# CHIP_dispv3_0.net
KiCad netlist of a schematic drawn in EAGLE
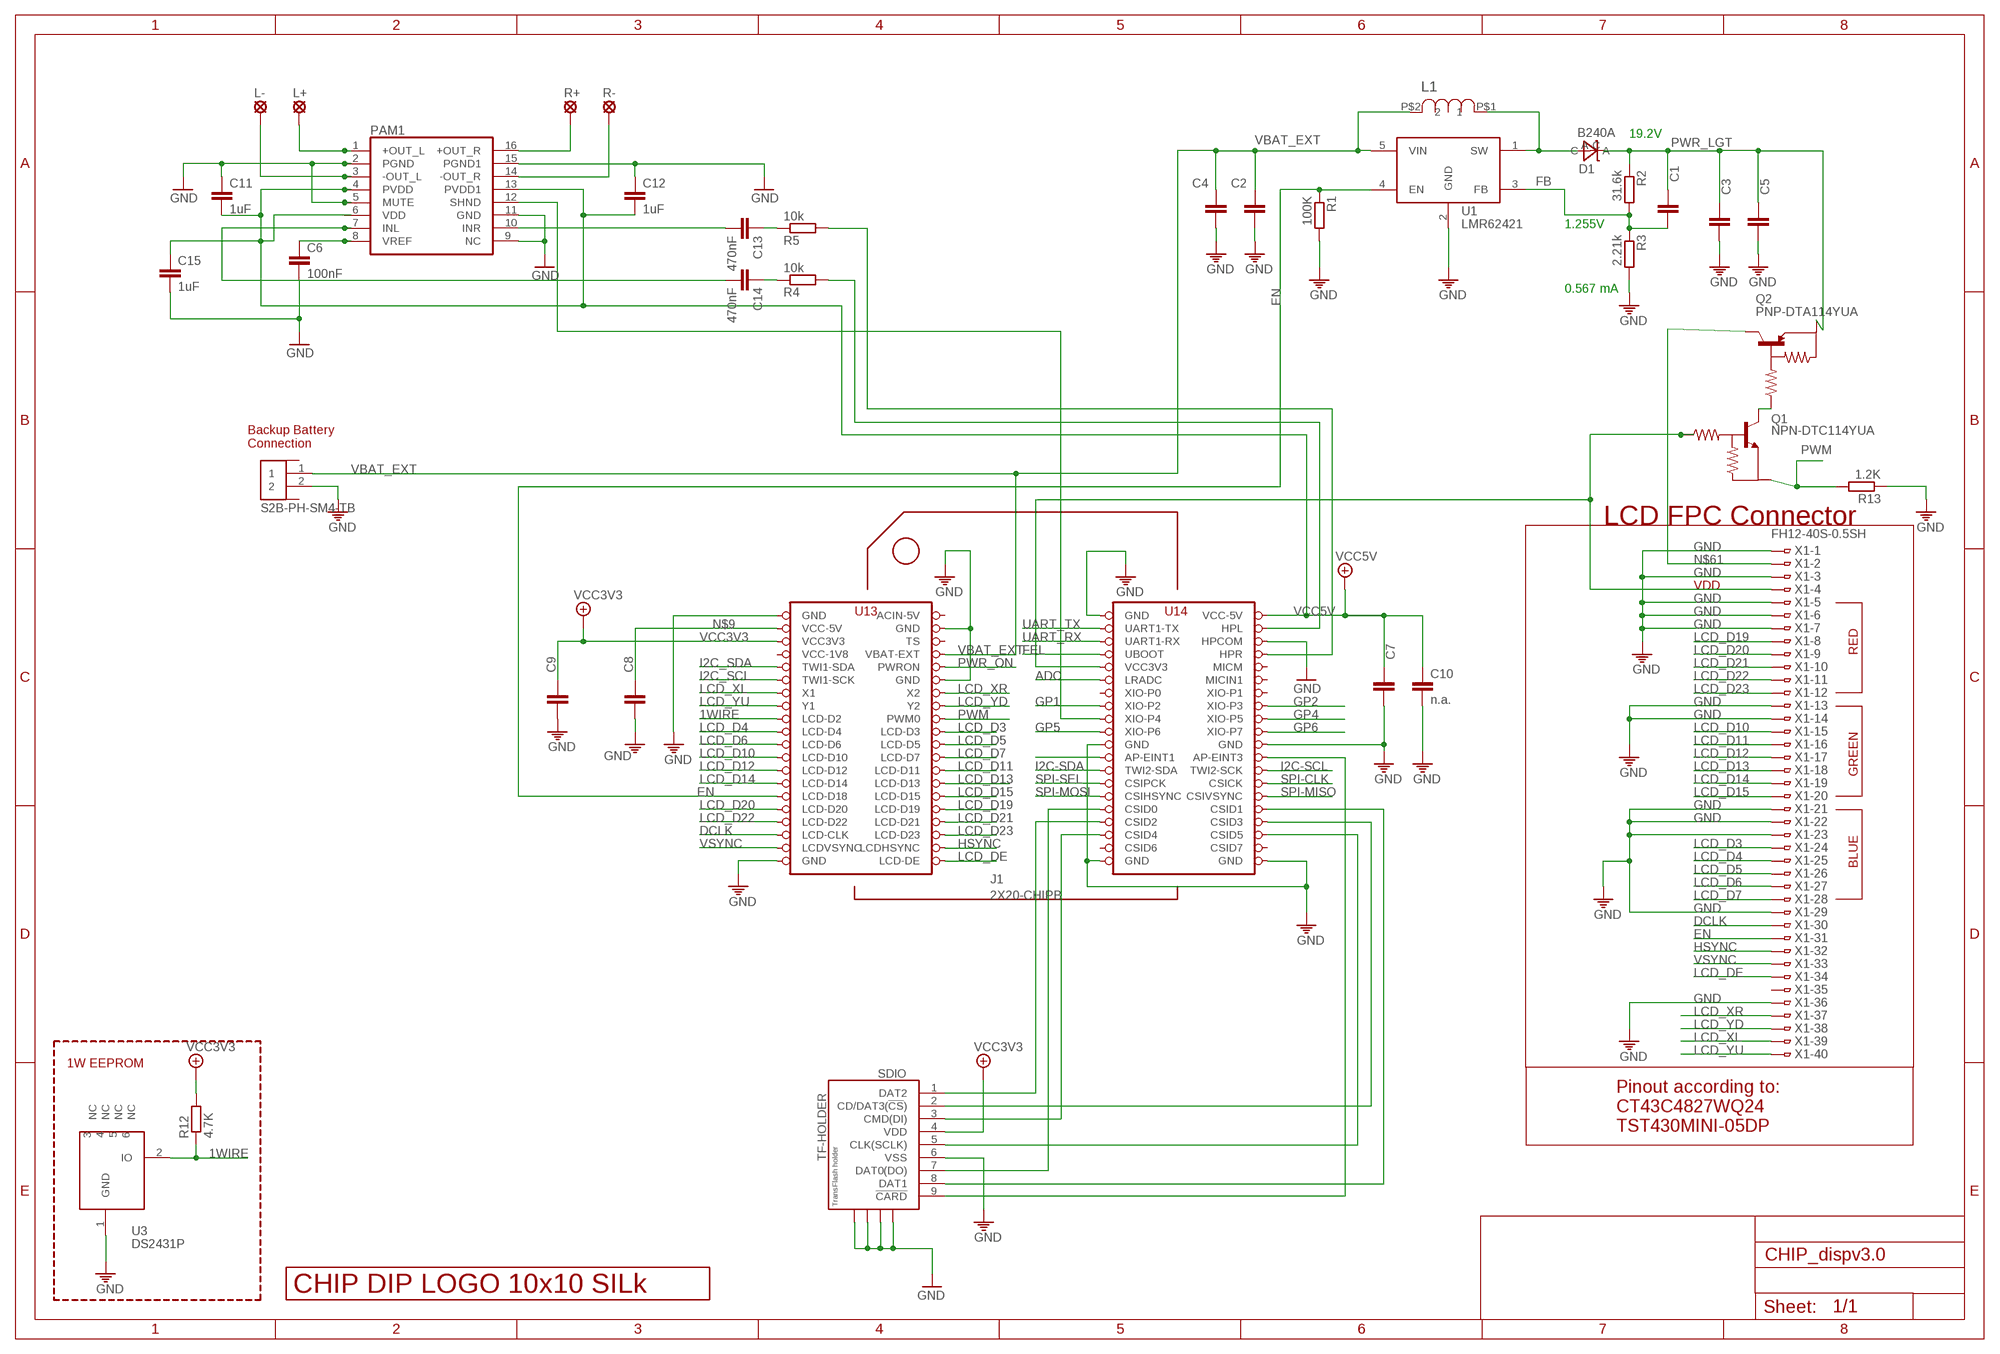
[diagram p0: schematic, sheet 1]

(export (version "E")
  (design (tool "Eeschema 10.0.6"))
  (components
    (comp (ref "C1")
      (value "220pF")
      (footprint "eagle-import:C0805")
      (libsource (lib "eagle-import") (part "C-EUC0805"))
    )
    (comp (ref "C2")
      (value "100nF")
      (footprint "eagle-import:C0805")
      (libsource (lib "eagle-import") (part "C-EUC0805"))
    )
    (comp (ref "C3")
      (value "100nF")
      (footprint "eagle-import:C0805")
      (libsource (lib "eagle-import") (part "C-EUC0805"))
    )
    (comp (ref "C4")
      (value "22uF")
      (footprint "eagle-import:C0805")
      (libsource (lib "eagle-import") (part "C-EUC0805"))
    )
    (comp (ref "C5")
      (value "22uF")
      (footprint "eagle-import:C0805")
      (libsource (lib "eagle-import") (part "C-EUC0805"))
    )
    (comp (ref "C6")
      (value "100nF")
      (footprint "eagle-import:C0805")
      (libsource (lib "eagle-import") (part "C-EUC0805"))
    )
    (comp (ref "C7")
      (value "n.a.")
      (footprint "eagle-import:C0805")
      (libsource (lib "eagle-import") (part "C-EUC0805"))
    )
    (comp (ref "C8")
      (value "100nF")
      (footprint "eagle-import:C0805")
      (libsource (lib "eagle-import") (part "C-EUC0805"))
    )
    (comp (ref "C9")
      (value "100nF")
      (footprint "eagle-import:C0805")
      (libsource (lib "eagle-import") (part "C-EUC0805"))
    )
    (comp (ref "C10")
      (value "n.a.")
      (footprint "eagle-import:C0805")
      (libsource (lib "eagle-import") (part "C-EUC0805"))
    )
    (comp (ref "C11")
      (value "1uF")
      (footprint "eagle-import:C0805")
      (libsource (lib "eagle-import") (part "C-EUC0805"))
    )
    (comp (ref "C12")
      (value "1uF")
      (footprint "eagle-import:C0805")
      (libsource (lib "eagle-import") (part "C-EUC0805"))
    )
    (comp (ref "C13")
      (value "470nF")
      (footprint "eagle-import:C0805")
      (libsource (lib "eagle-import") (part "C-EUC0805"))
    )
    (comp (ref "C14")
      (value "470nF")
      (footprint "eagle-import:C0805")
      (libsource (lib "eagle-import") (part "C-EUC0805"))
    )
    (comp (ref "C15")
      (value "1uF")
      (footprint "eagle-import:C0805")
      (libsource (lib "eagle-import") (part "C-EUC0805"))
    )
    (comp (ref "D1")
      (value "B240A")
      (footprint "eagle-import:DO-214AC")
      (fields (field (name "MFG") "DIGIKEY") (field (name "VENDOR_PART_NUMBER") "B240A-13-F"))
      (libsource (lib "eagle-import") (part "DIODE_SCHTKY_B240"))
    )
    (comp (ref "J1")
      (value "2X20-CHIPB")
      (footprint "eagle-import:2X20CHIP_SM")
      (libsource (lib "eagle-import") (part "2X20-CHIPB"))
    )
    (comp (ref "J3")
      (value "S2B-PH-SM4-TB")
      (footprint "eagle-import:S2B-PH-SM4-TB")
      (fields (field (name "MFG") "DIGIKEY") (field (name "VENDOR_PART_NUMBER") "S2B-PH-SM4-TB(LF)(SN)"))
      (libsource (lib "eagle-import") (part "S2B-PH-SM4-TB"))
    )
    (comp (ref "L+")
      (value "SE11")
      (footprint "eagle-import:SE11")
      (libsource (lib "eagle-import") (part "SE11"))
    )
    (comp (ref "L-")
      (value "SE11")
      (footprint "eagle-import:SE11")
      (libsource (lib "eagle-import") (part "SE11"))
    )
    (comp (ref "L1")
      (value "SRN6045-100M")
      (footprint "eagle-import:SRN6045")
      (fields (field (name "MFG") "DIGIKEY"))
      (libsource (lib "eagle-import") (part "SRN6045-100M"))
    )
    (comp (ref "PAM1")
      (value "PAM8403")
      (footprint "eagle-import:SOP-16")
      (libsource (lib "eagle-import") (part "PAM8403"))
    )
    (comp (ref "Q1")
      (value "NPN-DTC114YUA")
      (footprint "eagle-import:SOT323")
      (libsource (lib "eagle-import") (part "NPN-DTC114YUA"))
    )
    (comp (ref "Q2")
      (value "PNP-DTA114YUA")
      (footprint "eagle-import:SOT323")
      (libsource (lib "eagle-import") (part "PNP-DTA114YUA"))
    )
    (comp (ref "R+")
      (value "SE11")
      (footprint "eagle-import:SE11")
      (libsource (lib "eagle-import") (part "SE11"))
    )
    (comp (ref "R-")
      (value "SE11")
      (footprint "eagle-import:SE11")
      (libsource (lib "eagle-import") (part "SE11"))
    )
    (comp (ref "R1")
      (value "100K")
      (footprint "eagle-import:M0805")
      (libsource (lib "eagle-import") (part "R-EU_M0805"))
    )
    (comp (ref "R2")
      (value "31.6k")
      (footprint "eagle-import:M0805")
      (libsource (lib "eagle-import") (part "R-EU_M0805"))
    )
    (comp (ref "R3")
      (value "2.21k")
      (footprint "eagle-import:M0805")
      (libsource (lib "eagle-import") (part "R-EU_M0805"))
    )
    (comp (ref "R4")
      (value "10k")
      (footprint "eagle-import:R0805")
      (libsource (lib "eagle-import") (part "R-EU_R0805"))
    )
    (comp (ref "R5")
      (value "10k")
      (footprint "eagle-import:R0805")
      (libsource (lib "eagle-import") (part "R-EU_R0805"))
    )
    (comp (ref "R12")
      (value "4.7K")
      (footprint "eagle-import:M0805")
      (libsource (lib "eagle-import") (part "R-EU_M0805"))
    )
    (comp (ref "R13")
      (value "1.2K")
      (footprint "eagle-import:M0805")
      (libsource (lib "eagle-import") (part "R-EU_M0805"))
    )
    (comp (ref "SDIO")
      (value "TF-HOLDER")
      (footprint "eagle-import:TF-PULL")
      (libsource (lib "eagle-import") (part "TF-HOLDER"))
    )
    (comp (ref "U$2")
      (value "LOGO_10X10_SILK")
      (footprint "eagle-import:LOGO2_10X10_SILK")
      (libsource (lib "eagle-import") (part "LOGO_10X10_SILK"))
    )
    (comp (ref "U1")
      (value "LMR62421")
      (footprint "eagle-import:SOT23-5")
      (fields (field (name "MFG") "DIGIKEY") (field (name "VENDOR_PART_NUMBER") "LMR62421XMFE/NOPB"))
      (libsource (lib "eagle-import") (part "LMR62421"))
    )
    (comp (ref "U3")
      (value "DS2431P")
      (footprint "eagle-import:TSOC6")
      (fields (field (name "MFG") "DIGIKEY") (field (name "VENDOR_PART_NUMBER") "DS2431P+T&R"))
      (libsource (lib "eagle-import") (part "DS2431P"))
    )
    (comp (ref "X1")
      (value "FH12-40S-0.5SH")
      (footprint "eagle-import:FH12-40S-0.5SH")
      (fields (field (name "MFG") "DIGIKEY") (field (name "VENDOR_PART_NUMBER") "FH12-40S-0.5SH(55)"))
      (libsource (lib "eagle-import") (part "FH12-40S-0.5SH"))
    )
  )
  (nets
    (net (code "1") (name "/1WIRE") (class "Default")
      (node (ref "J1") (pin "LCD-D2") (pinfunction "LCD-D2_LCD-D2") (pintype "passive"))
      (node (ref "R12") (pin "1") (pinfunction "1_1") (pintype "passive"))
      (node (ref "U3") (pin "2") (pinfunction "IO_2") (pintype "bidirectional"))
    )
    (net (code "2") (name "/ADC") (class "Default")
      (node (ref "J1") (pin "LRADC") (pinfunction "LRADC_LRADC") (pintype "passive"))
    )
    (net (code "3") (name "/DCLK") (class "Default")
      (node (ref "J1") (pin "LCD-CLK") (pinfunction "LCD-CLK_LCD-CLK") (pintype "passive"))
      (node (ref "X1") (pin "30") (pinfunction "1_30") (pintype "passive"))
    )
    (net (code "4") (name "/EN") (class "Default")
      (node (ref "J1") (pin "LCD-D18") (pinfunction "LCD-D18_LCD-D18") (pintype "passive"))
      (node (ref "R1") (pin "1") (pinfunction "1_1") (pintype "passive"))
      (node (ref "U1") (pin "4") (pinfunction "EN_4") (pintype "bidirectional"))
      (node (ref "X1") (pin "31") (pinfunction "1_31") (pintype "passive"))
    )
    (net (code "5") (name "/FB") (class "Default")
      (node (ref "C1") (pin "2") (pinfunction "2_2") (pintype "passive"))
      (node (ref "R2") (pin "2") (pinfunction "2_2") (pintype "passive"))
      (node (ref "R3") (pin "1") (pinfunction "1_1") (pintype "passive"))
      (node (ref "U1") (pin "3") (pinfunction "FB_3") (pintype "bidirectional"))
    )
    (net (code "6") (name "/FEL") (class "Default")
      (node (ref "J1") (pin "FEL") (pinfunction "UBOOT_FEL") (pintype "passive"))
    )
    (net (code "7") (name "/GP1") (class "Default")
      (node (ref "J1") (pin "XIO-P2") (pinfunction "XIO-P2_XIO-P2") (pintype "passive"))
    )
    (net (code "8") (name "/GP2") (class "Default")
      (node (ref "J1") (pin "XIO-P3") (pinfunction "XIO-P3_XIO-P3") (pintype "passive"))
    )
    (net (code "9") (name "/GP4") (class "Default")
      (node (ref "J1") (pin "XIO-P5") (pinfunction "XIO-P5_XIO-P5") (pintype "passive"))
    )
    (net (code "10") (name "/GP5") (class "Default")
      (node (ref "J1") (pin "XIO-P6") (pinfunction "XIO-P6_XIO-P6") (pintype "passive"))
    )
    (net (code "11") (name "/GP6") (class "Default")
      (node (ref "J1") (pin "XIO-P7") (pinfunction "XIO-P7_XIO-P7") (pintype "passive"))
    )
    (net (code "12") (name "/HSYNC") (class "Default")
      (node (ref "J1") (pin "LCD-HSYNC") (pinfunction "LCDHSYNC_LCD-HSYNC") (pintype "passive"))
      (node (ref "X1") (pin "32") (pinfunction "1_32") (pintype "passive"))
    )
    (net (code "13") (name "/I2C-SCL") (class "Default")
      (node (ref "J1") (pin "TWI2-SCK") (pinfunction "TWI2-SCK_TWI2-SCK") (pintype "passive"))
    )
    (net (code "14") (name "/I2C-SDA") (class "Default")
      (node (ref "J1") (pin "TWI2-SDA") (pinfunction "TWI2-SDA_TWI2-SDA") (pintype "passive"))
    )
    (net (code "15") (name "/I2C_SCL") (class "Default")
      (node (ref "J1") (pin "TWI1-SCK") (pinfunction "TWI1-SCK_TWI1-SCK") (pintype "passive"))
    )
    (net (code "16") (name "/I2C_SDA") (class "Default")
      (node (ref "J1") (pin "TWI1-SDA") (pinfunction "TWI1-SDA_TWI1-SDA") (pintype "passive"))
    )
    (net (code "17") (name "/LCD_D3") (class "Default")
      (node (ref "J1") (pin "LCD-D3") (pinfunction "LCD-D3_LCD-D3") (pintype "passive"))
      (node (ref "X1") (pin "24") (pinfunction "1_24") (pintype "passive"))
    )
    (net (code "18") (name "/LCD_D4") (class "Default")
      (node (ref "J1") (pin "LCD-D4") (pinfunction "LCD-D4_LCD-D4") (pintype "passive"))
      (node (ref "X1") (pin "25") (pinfunction "1_25") (pintype "passive"))
    )
    (net (code "19") (name "/LCD_D5") (class "Default")
      (node (ref "J1") (pin "LCD-D5") (pinfunction "LCD-D5_LCD-D5") (pintype "passive"))
      (node (ref "X1") (pin "26") (pinfunction "1_26") (pintype "passive"))
    )
    (net (code "20") (name "/LCD_D6") (class "Default")
      (node (ref "J1") (pin "LCD-D6") (pinfunction "LCD-D6_LCD-D6") (pintype "passive"))
      (node (ref "X1") (pin "27") (pinfunction "1_27") (pintype "passive"))
    )
    (net (code "21") (name "/LCD_D7") (class "Default")
      (node (ref "J1") (pin "LCD-D7") (pinfunction "LCD-D7_LCD-D7") (pintype "passive"))
      (node (ref "X1") (pin "28") (pinfunction "1_28") (pintype "passive"))
    )
    (net (code "22") (name "/LCD_D10") (class "Default")
      (node (ref "J1") (pin "LCD-D10") (pinfunction "LCD-D10_LCD-D10") (pintype "passive"))
      (node (ref "X1") (pin "15") (pinfunction "1_15") (pintype "passive"))
    )
    (net (code "23") (name "/LCD_D11") (class "Default")
      (node (ref "J1") (pin "LCD-D11") (pinfunction "LCD-D11_LCD-D11") (pintype "passive"))
      (node (ref "X1") (pin "16") (pinfunction "1_16") (pintype "passive"))
    )
    (net (code "24") (name "/LCD_D12") (class "Default")
      (node (ref "J1") (pin "LCD-D12") (pinfunction "LCD-D12_LCD-D12") (pintype "passive"))
      (node (ref "X1") (pin "17") (pinfunction "1_17") (pintype "passive"))
    )
    (net (code "25") (name "/LCD_D13") (class "Default")
      (node (ref "J1") (pin "LCD-D13") (pinfunction "LCD-D13_LCD-D13") (pintype "passive"))
      (node (ref "X1") (pin "18") (pinfunction "1_18") (pintype "passive"))
    )
    (net (code "26") (name "/LCD_D14") (class "Default")
      (node (ref "J1") (pin "LCD-D14") (pinfunction "LCD-D14_LCD-D14") (pintype "passive"))
      (node (ref "X1") (pin "19") (pinfunction "1_19") (pintype "passive"))
    )
    (net (code "27") (name "/LCD_D15") (class "Default")
      (node (ref "J1") (pin "LCD-D15") (pinfunction "LCD-D15_LCD-D15") (pintype "passive"))
      (node (ref "X1") (pin "20") (pinfunction "1_20") (pintype "passive"))
    )
    (net (code "28") (name "/LCD_D19") (class "Default")
      (node (ref "J1") (pin "LCD-D19") (pinfunction "LCD-D19_LCD-D19") (pintype "passive"))
      (node (ref "X1") (pin "8") (pinfunction "1_8") (pintype "passive"))
    )
    (net (code "29") (name "/LCD_D20") (class "Default")
      (node (ref "J1") (pin "LCD-D20") (pinfunction "LCD-D20_LCD-D20") (pintype "passive"))
      (node (ref "X1") (pin "9") (pinfunction "1_9") (pintype "passive"))
    )
    (net (code "30") (name "/LCD_D21") (class "Default")
      (node (ref "J1") (pin "LCD-D21") (pinfunction "LCD-D21_LCD-D21") (pintype "passive"))
      (node (ref "X1") (pin "10") (pinfunction "1_10") (pintype "passive"))
    )
    (net (code "31") (name "/LCD_D22") (class "Default")
      (node (ref "J1") (pin "LCD-D22") (pinfunction "LCD-D22_LCD-D22") (pintype "passive"))
      (node (ref "X1") (pin "11") (pinfunction "1_11") (pintype "passive"))
    )
    (net (code "32") (name "/LCD_D23") (class "Default")
      (node (ref "J1") (pin "LCD-D23") (pinfunction "LCD-D23_LCD-D23") (pintype "passive"))
      (node (ref "X1") (pin "12") (pinfunction "1_12") (pintype "passive"))
    )
    (net (code "33") (name "/LCD_DE") (class "Default")
      (node (ref "J1") (pin "LCD-DE") (pinfunction "LCD-DE_LCD-DE") (pintype "passive"))
      (node (ref "X1") (pin "34") (pinfunction "1_34") (pintype "passive"))
    )
    (net (code "34") (name "/LCD_XL") (class "Default")
      (node (ref "J1") (pin "X1") (pinfunction "X1_X1") (pintype "passive"))
      (node (ref "X1") (pin "39") (pinfunction "1_39") (pintype "passive"))
    )
    (net (code "35") (name "/LCD_XR") (class "Default")
      (node (ref "J1") (pin "X2") (pinfunction "X2_X2") (pintype "passive"))
      (node (ref "X1") (pin "37") (pinfunction "1_37") (pintype "passive"))
    )
    (net (code "36") (name "/LCD_YD") (class "Default")
      (node (ref "J1") (pin "Y2") (pinfunction "Y2_Y2") (pintype "passive"))
      (node (ref "X1") (pin "38") (pinfunction "1_38") (pintype "passive"))
    )
    (net (code "37") (name "/LCD_YU") (class "Default")
      (node (ref "J1") (pin "Y1") (pinfunction "Y1_Y1") (pintype "passive"))
      (node (ref "X1") (pin "40") (pinfunction "1_40") (pintype "passive"))
    )
    (net (code "38") (name "/N$9") (class "Default")
      (node (ref "C8") (pin "1") (pinfunction "1_1") (pintype "passive"))
      (node (ref "J1") (pin "VCC5V@0") (pinfunction "VCC-5V_VCC5V@0") (pintype "power_in"))
    )
    (net (code "39") (name "/N$61") (class "Default")
      (node (ref "Q2") (pin "3") (pinfunction "OUT_3") (pintype "passive"))
      (node (ref "X1") (pin "2") (pinfunction "1_2") (pintype "passive"))
    )
    (net (code "40") (name "/PWM") (class "Default")
      (node (ref "J1") (pin "PWM0") (pinfunction "PWM0_PWM0") (pintype "passive"))
      (node (ref "Q1") (pin "2") (pinfunction "GND_2") (pintype "passive"))
      (node (ref "R13") (pin "2") (pinfunction "2_2") (pintype "passive"))
    )
    (net (code "41") (name "/PWR_LGT") (class "Default")
      (node (ref "C1") (pin "1") (pinfunction "1_1") (pintype "passive"))
      (node (ref "C3") (pin "1") (pinfunction "1_1") (pintype "passive"))
      (node (ref "C5") (pin "1") (pinfunction "1_1") (pintype "passive"))
      (node (ref "D1") (pin "C") (pinfunction "C_C") (pintype "bidirectional"))
      (node (ref "Q2") (pin "2") (pinfunction "GND_2") (pintype "passive"))
      (node (ref "R2") (pin "1") (pinfunction "1_1") (pintype "passive"))
    )
    (net (code "42") (name "/PWR_ON") (class "Default")
      (node (ref "J1") (pin "PWRON") (pinfunction "PWRON_PWRON") (pintype "passive"))
    )
    (net (code "43") (name "/SPI-CLK") (class "Default")
      (node (ref "J1") (pin "CSICK") (pinfunction "CSICK_CSICK") (pintype "passive"))
    )
    (net (code "44") (name "/SPI-MISO") (class "Default")
      (node (ref "J1") (pin "CSIVSYNC") (pinfunction "CSIVSYNC_CSIVSYNC") (pintype "passive"))
    )
    (net (code "45") (name "/SPI-MOSI") (class "Default")
      (node (ref "J1") (pin "CSIHSYNC") (pinfunction "CSIHSYNC_CSIHSYNC") (pintype "passive"))
    )
    (net (code "46") (name "/SPI-SEL") (class "Default")
      (node (ref "J1") (pin "CSIPCK") (pinfunction "CSIPCK_CSIPCK") (pintype "passive"))
    )
    (net (code "47") (name "/UART_RX") (class "Default")
      (node (ref "J1") (pin "UART1-RX") (pinfunction "UART1-RX_UART1-RX") (pintype "passive"))
    )
    (net (code "48") (name "/UART_TX") (class "Default")
      (node (ref "J1") (pin "UART1-TX") (pinfunction "UART1-TX_UART1-TX") (pintype "passive"))
    )
    (net (code "49") (name "/VBAT_EXT") (class "Default")
      (node (ref "C2") (pin "1") (pinfunction "1_1") (pintype "passive"))
      (node (ref "C4") (pin "1") (pinfunction "1_1") (pintype "passive"))
      (node (ref "J1") (pin "BAT") (pinfunction "VBAT-EXT_BAT") (pintype "passive"))
      (node (ref "J3") (pin "1") (pinfunction "1_1") (pintype "bidirectional"))
      (node (ref "L1") (pin "P$2") (pinfunction "2_P$2") (pintype "passive"))
      (node (ref "U1") (pin "5") (pinfunction "VIN_5") (pintype "bidirectional"))
    )
    (net (code "50") (name "/VCC-1V8") (class "Default")
      (node (ref "J1") (pin "VCC1V8") (pinfunction "VCC-1V8_VCC1V8") (pintype "power_in"))
    )
    (net (code "51") (name "/VSYNC") (class "Default")
      (node (ref "J1") (pin "LCD-VSYNC") (pinfunction "LCDVSYNC_LCD-VSYNC") (pintype "passive"))
      (node (ref "X1") (pin "33") (pinfunction "1_33") (pintype "passive"))
    )
    (net (code "52") (name "GND") (class "Default")
      (node (ref "C10") (pin "2") (pinfunction "2_2") (pintype "passive"))
      (node (ref "C11") (pin "1") (pinfunction "1_1") (pintype "passive"))
      (node (ref "C12") (pin "1") (pinfunction "1_1") (pintype "passive"))
      (node (ref "C15") (pin "2") (pinfunction "2_2") (pintype "passive"))
      (node (ref "C2") (pin "2") (pinfunction "2_2") (pintype "passive"))
      (node (ref "C3") (pin "2") (pinfunction "2_2") (pintype "passive"))
      (node (ref "C4") (pin "2") (pinfunction "2_2") (pintype "passive"))
      (node (ref "C5") (pin "2") (pinfunction "2_2") (pintype "passive"))
      (node (ref "C6") (pin "2") (pinfunction "2_2") (pintype "passive"))
      (node (ref "C7") (pin "2") (pinfunction "2_2") (pintype "passive"))
      (node (ref "C8") (pin "2") (pinfunction "2_2") (pintype "passive"))
      (node (ref "C9") (pin "2") (pinfunction "2_2") (pintype "passive"))
      (node (ref "J1") (pin "GND@1") (pinfunction "GND_GND@1") (pintype "power_in"))
      (node (ref "J1") (pin "GND@10") (pinfunction "GND_GND@10") (pintype "power_in"))
      (node (ref "J1") (pin "GND@2") (pinfunction "GND_GND@2") (pintype "power_in"))
      (node (ref "J1") (pin "GND@3") (pinfunction "GND_GND@3") (pintype "power_in"))
      (node (ref "J1") (pin "GND@4") (pinfunction "GND_GND@4") (pintype "power_in"))
      (node (ref "J1") (pin "GND@5") (pinfunction "GND_GND@5") (pintype "power_in"))
      (node (ref "J1") (pin "GND@6") (pinfunction "GND_GND@6") (pintype "power_in"))
      (node (ref "J1") (pin "GND@7") (pinfunction "GND_GND@7") (pintype "power_in"))
      (node (ref "J1") (pin "GND@8") (pinfunction "GND_GND@8") (pintype "power_in"))
      (node (ref "J1") (pin "HPCOM") (pinfunction "HPCOM_HPCOM") (pintype "passive"))
      (node (ref "J3") (pin "2") (pinfunction "2_2") (pintype "bidirectional"))
      (node (ref "PAM1") (pin "11") (pinfunction "GND_11") (pintype "output"))
      (node (ref "PAM1") (pin "15") (pinfunction "PGND1_15") (pintype "output"))
      (node (ref "PAM1") (pin "2") (pinfunction "PGND_2") (pintype "input"))
      (node (ref "PAM1") (pin "5") (pinfunction "MUTE_5") (pintype "input"))
      (node (ref "PAM1") (pin "9") (pinfunction "NC_9") (pintype "output"))
      (node (ref "R1") (pin "2") (pinfunction "2_2") (pintype "passive"))
      (node (ref "R13") (pin "1") (pinfunction "1_1") (pintype "passive"))
      (node (ref "R3") (pin "2") (pinfunction "2_2") (pintype "passive"))
      (node (ref "SDIO") (pin "6") (pinfunction "VSS_6") (pintype "power_in"))
      (node (ref "SDIO") (pin "S1") (pinfunction "S1_S1") (pintype "passive"))
      (node (ref "SDIO") (pin "S2") (pinfunction "S2_S2") (pintype "passive"))
      (node (ref "SDIO") (pin "S3") (pinfunction "S3_S3") (pintype "passive"))
      (node (ref "SDIO") (pin "S4") (pinfunction "S4_S4") (pintype "passive"))
      (node (ref "U1") (pin "2") (pinfunction "GND_2") (pintype "bidirectional"))
      (node (ref "U3") (pin "1") (pinfunction "GND_1") (pintype "bidirectional"))
      (node (ref "X1") (pin "1") (pinfunction "1_1") (pintype "passive"))
      (node (ref "X1") (pin "13") (pinfunction "1_13") (pintype "passive"))
      (node (ref "X1") (pin "14") (pinfunction "1_14") (pintype "passive"))
      (node (ref "X1") (pin "21") (pinfunction "1_21") (pintype "passive"))
      (node (ref "X1") (pin "22") (pinfunction "1_22") (pintype "passive"))
      (node (ref "X1") (pin "23") (pinfunction "1_23") (pintype "passive"))
      (node (ref "X1") (pin "29") (pinfunction "1_29") (pintype "passive"))
      (node (ref "X1") (pin "3") (pinfunction "1_3") (pintype "passive"))
      (node (ref "X1") (pin "36") (pinfunction "1_36") (pintype "passive"))
      (node (ref "X1") (pin "5") (pinfunction "1_5") (pintype "passive"))
      (node (ref "X1") (pin "6") (pinfunction "1_6") (pintype "passive"))
      (node (ref "X1") (pin "7") (pinfunction "1_7") (pintype "passive"))
    )
    (net (code "53") (name "Net-(C13-Pad1)") (class "Default")
      (node (ref "C13") (pin "1") (pinfunction "1_1") (pintype "passive"))
      (node (ref "R5") (pin "1") (pinfunction "1_1") (pintype "passive"))
    )
    (net (code "54") (name "Net-(C14-Pad1)") (class "Default")
      (node (ref "C14") (pin "1") (pinfunction "1_1") (pintype "passive"))
      (node (ref "R4") (pin "1") (pinfunction "1_1") (pintype "passive"))
    )
    (net (code "55") (name "Net-(J1-PadHPL)") (class "Default")
      (node (ref "J1") (pin "HPL") (pinfunction "HPL_HPL") (pintype "passive"))
      (node (ref "R4") (pin "2") (pinfunction "2_2") (pintype "passive"))
    )
    (net (code "56") (name "Net-(J1-PadHPR)") (class "Default")
      (node (ref "J1") (pin "HPR") (pinfunction "HPR_HPR") (pintype "passive"))
      (node (ref "R5") (pin "2") (pinfunction "2_2") (pintype "passive"))
    )
    (net (code "57") (name "Net-(L1-1)") (class "Default")
      (node (ref "D1") (pin "A") (pinfunction "A_A") (pintype "bidirectional"))
      (node (ref "L1") (pin "P$1") (pinfunction "1_P$1") (pintype "passive"))
      (node (ref "U1") (pin "1") (pinfunction "SW_1") (pintype "bidirectional"))
    )
    (net (code "58") (name "Net-(PAM1-+OUT_L)") (class "Default")
      (node (ref "L+") (pin "MP") (pinfunction "MP_MP") (pintype "passive"))
      (node (ref "PAM1") (pin "1") (pinfunction "+OUT_L_1") (pintype "input"))
    )
    (net (code "59") (name "Net-(PAM1-+OUT_R)") (class "Default")
      (node (ref "PAM1") (pin "16") (pinfunction "+OUT_R_16") (pintype "output"))
      (node (ref "R+") (pin "MP") (pinfunction "MP_MP") (pintype "passive"))
    )
    (net (code "60") (name "Net-(PAM1--OUT_L)") (class "Default")
      (node (ref "L-") (pin "MP") (pinfunction "MP_MP") (pintype "passive"))
      (node (ref "PAM1") (pin "3") (pinfunction "-OUT_L_3") (pintype "input"))
    )
    (net (code "61") (name "Net-(PAM1--OUT_R)") (class "Default")
      (node (ref "PAM1") (pin "14") (pinfunction "-OUT_R_14") (pintype "output"))
      (node (ref "R-") (pin "MP") (pinfunction "MP_MP") (pintype "passive"))
    )
    (net (code "62") (name "Net-(PAM1-INL)") (class "Default")
      (node (ref "C14") (pin "2") (pinfunction "2_2") (pintype "passive"))
      (node (ref "PAM1") (pin "7") (pinfunction "INL_7") (pintype "input"))
    )
    (net (code "63") (name "Net-(PAM1-INR)") (class "Default")
      (node (ref "C13") (pin "2") (pinfunction "2_2") (pintype "passive"))
      (node (ref "PAM1") (pin "10") (pinfunction "INR_10") (pintype "output"))
    )
    (net (code "64") (name "Net-(PAM1-SHND)") (class "Default")
      (node (ref "J1") (pin "XIO-P4") (pinfunction "XIO-P4_XIO-P4") (pintype "passive"))
      (node (ref "PAM1") (pin "12") (pinfunction "SHND_12") (pintype "output"))
    )
    (net (code "65") (name "Net-(PAM1-VREF)") (class "Default")
      (node (ref "C6") (pin "1") (pinfunction "1_1") (pintype "passive"))
      (node (ref "PAM1") (pin "8") (pinfunction "VREF_8") (pintype "input"))
    )
    (net (code "66") (name "Net-(Q1-IN)") (class "Default")
      (node (ref "J1") (pin "VCC3V3@1") (pinfunction "VCC3V3_VCC3V3@1") (pintype "power_in"))
      (node (ref "Q1") (pin "1") (pinfunction "IN_1") (pintype "passive"))
      (node (ref "X1") (pin "4") (pinfunction "1_4") (pintype "passive"))
    )
    (net (code "67") (name "Net-(Q1-OUT)") (class "Default")
      (node (ref "Q1") (pin "3") (pinfunction "OUT_3") (pintype "passive"))
      (node (ref "Q2") (pin "1") (pinfunction "IN_1") (pintype "passive"))
    )
    (net (code "68") (name "Net-(SDIO-CD{slash}DAT3(~{CS}))") (class "Default")
      (node (ref "J1") (pin "CSID3") (pinfunction "CSID3_CSID3") (pintype "passive"))
      (node (ref "SDIO") (pin "2") (pinfunction "CD/DAT3(~{CS})_2") (pintype "bidirectional"))
    )
    (net (code "69") (name "Net-(SDIO-CLK(SCLK))") (class "Default")
      (node (ref "J1") (pin "CSID5") (pinfunction "CSID5_CSID5") (pintype "passive"))
      (node (ref "SDIO") (pin "5") (pinfunction "CLK(SCLK)_5") (pintype "input"))
    )
    (net (code "70") (name "Net-(SDIO-CMD(DI))") (class "Default")
      (node (ref "J1") (pin "CSID4") (pinfunction "CSID4_CSID4") (pintype "passive"))
      (node (ref "SDIO") (pin "3") (pinfunction "CMD(DI)_3") (pintype "bidirectional"))
    )
    (net (code "71") (name "Net-(SDIO-DAT0(DO))") (class "Default")
      (node (ref "J1") (pin "CSID0") (pinfunction "CSID0_CSID0") (pintype "passive"))
      (node (ref "SDIO") (pin "7") (pinfunction "DAT0(DO)_7") (pintype "bidirectional"))
    )
    (net (code "72") (name "Net-(SDIO-DAT1)") (class "Default")
      (node (ref "J1") (pin "CSID1") (pinfunction "CSID1_CSID1") (pintype "passive"))
      (node (ref "SDIO") (pin "8") (pinfunction "DAT1_8") (pintype "bidirectional"))
    )
    (net (code "73") (name "Net-(SDIO-DAT2)") (class "Default")
      (node (ref "J1") (pin "CSID2") (pinfunction "CSID2_CSID2") (pintype "passive"))
      (node (ref "SDIO") (pin "1") (pinfunction "DAT2_1") (pintype "bidirectional"))
    )
    (net (code "74") (name "Net-(SDIO-~{CARD})") (class "Default")
      (node (ref "J1") (pin "AP-EINT3") (pinfunction "AP-EINT3_AP-EINT3") (pintype "passive"))
      (node (ref "SDIO") (pin "9") (pinfunction "~{CARD}_9") (pintype "passive"))
    )
    (net (code "75") (name "VCC3V3") (class "Default")
      (node (ref "C9") (pin "1") (pinfunction "1_1") (pintype "passive"))
      (node (ref "J1") (pin "VCC3V3") (pinfunction "VCC3V3_VCC3V3") (pintype "power_in"))
      (node (ref "R12") (pin "2") (pinfunction "2_2") (pintype "passive"))
      (node (ref "SDIO") (pin "4") (pinfunction "VDD_4") (pintype "power_in"))
    )
    (net (code "76") (name "VCC5V") (class "Default")
      (node (ref "C10") (pin "1") (pinfunction "1_1") (pintype "passive"))
      (node (ref "C11") (pin "2") (pinfunction "2_2") (pintype "passive"))
      (node (ref "C12") (pin "2") (pinfunction "2_2") (pintype "passive"))
      (node (ref "C15") (pin "1") (pinfunction "1_1") (pintype "passive"))
      (node (ref "C7") (pin "1") (pinfunction "1_1") (pintype "passive"))
      (node (ref "J1") (pin "VCC5V@1") (pinfunction "VCC-5V_VCC5V@1") (pintype "power_in"))
      (node (ref "PAM1") (pin "13") (pinfunction "PVDD1_13") (pintype "output"))
      (node (ref "PAM1") (pin "4") (pinfunction "PVDD_4") (pintype "input"))
      (node (ref "PAM1") (pin "6") (pinfunction "VDD_6") (pintype "input"))
    )
    (net (code "77") (name "unconnected-(J1-ACIN-5V-PadCHG-IN)") (class "Default")
      (node (ref "J1") (pin "CHG-IN") (pinfunction "ACIN-5V_CHG-IN") (pintype "passive"))
    )
    (net (code "78") (name "unconnected-(J1-PadAP-EINT1)") (class "Default")
      (node (ref "J1") (pin "AP-EINT1") (pinfunction "AP-EINT1_AP-EINT1") (pintype "passive"))
    )
    (net (code "79") (name "unconnected-(J1-PadCSID6)") (class "Default")
      (node (ref "J1") (pin "CSID6") (pinfunction "CSID6_CSID6") (pintype "passive"))
    )
    (net (code "80") (name "unconnected-(J1-PadCSID7)") (class "Default")
      (node (ref "J1") (pin "CSID7") (pinfunction "CSID7_CSID7") (pintype "passive"))
    )
    (net (code "81") (name "unconnected-(J1-PadMICIN1)") (class "Default")
      (node (ref "J1") (pin "MICIN1") (pinfunction "MICIN1_MICIN1") (pintype "passive"))
    )
    (net (code "82") (name "unconnected-(J1-PadMICM)") (class "Default")
      (node (ref "J1") (pin "MICM") (pinfunction "MICM_MICM") (pintype "passive"))
    )
    (net (code "83") (name "unconnected-(J1-PadTS)") (class "Default")
      (node (ref "J1") (pin "TS") (pinfunction "TS_TS") (pintype "passive"))
    )
    (net (code "84") (name "unconnected-(J1-PadXIO-P0)") (class "Default")
      (node (ref "J1") (pin "XIO-P0") (pinfunction "XIO-P0_XIO-P0") (pintype "passive"))
    )
    (net (code "85") (name "unconnected-(J1-PadXIO-P1)") (class "Default")
      (node (ref "J1") (pin "XIO-P1") (pinfunction "XIO-P1_XIO-P1") (pintype "passive"))
    )
    (net (code "86") (name "unconnected-(J3-PadMNT1)") (class "Default")
      (node (ref "J3") (pin "MNT1") (pinfunction "MNT1_MNT1") (pintype "no_connect"))
    )
    (net (code "87") (name "unconnected-(J3-PadMNT2)") (class "Default")
      (node (ref "J3") (pin "MNT2") (pinfunction "MNT2_MNT2") (pintype "no_connect"))
    )
    (net (code "88") (name "unconnected-(U3-NC-Pad3)") (class "Default")
      (node (ref "U3") (pin "3") (pinfunction "NC_3") (pintype "bidirectional"))
    )
    (net (code "89") (name "unconnected-(U3-NC-Pad4)") (class "Default")
      (node (ref "U3") (pin "4") (pinfunction "NC_4") (pintype "bidirectional"))
    )
    (net (code "90") (name "unconnected-(U3-NC-Pad5)") (class "Default")
      (node (ref "U3") (pin "5") (pinfunction "NC_5") (pintype "bidirectional"))
    )
    (net (code "91") (name "unconnected-(U3-NC-Pad6)") (class "Default")
      (node (ref "U3") (pin "6") (pinfunction "NC_6") (pintype "bidirectional"))
    )
    (net (code "92") (name "unconnected-(X1AC-1-Pad35)") (class "Default")
      (node (ref "X1") (pin "35") (pinfunction "1_35") (pintype "passive"))
    )
  )
)
